# snow_depth_gauge_2D.net
KiCad netlist of a schematic drawn in EAGLE
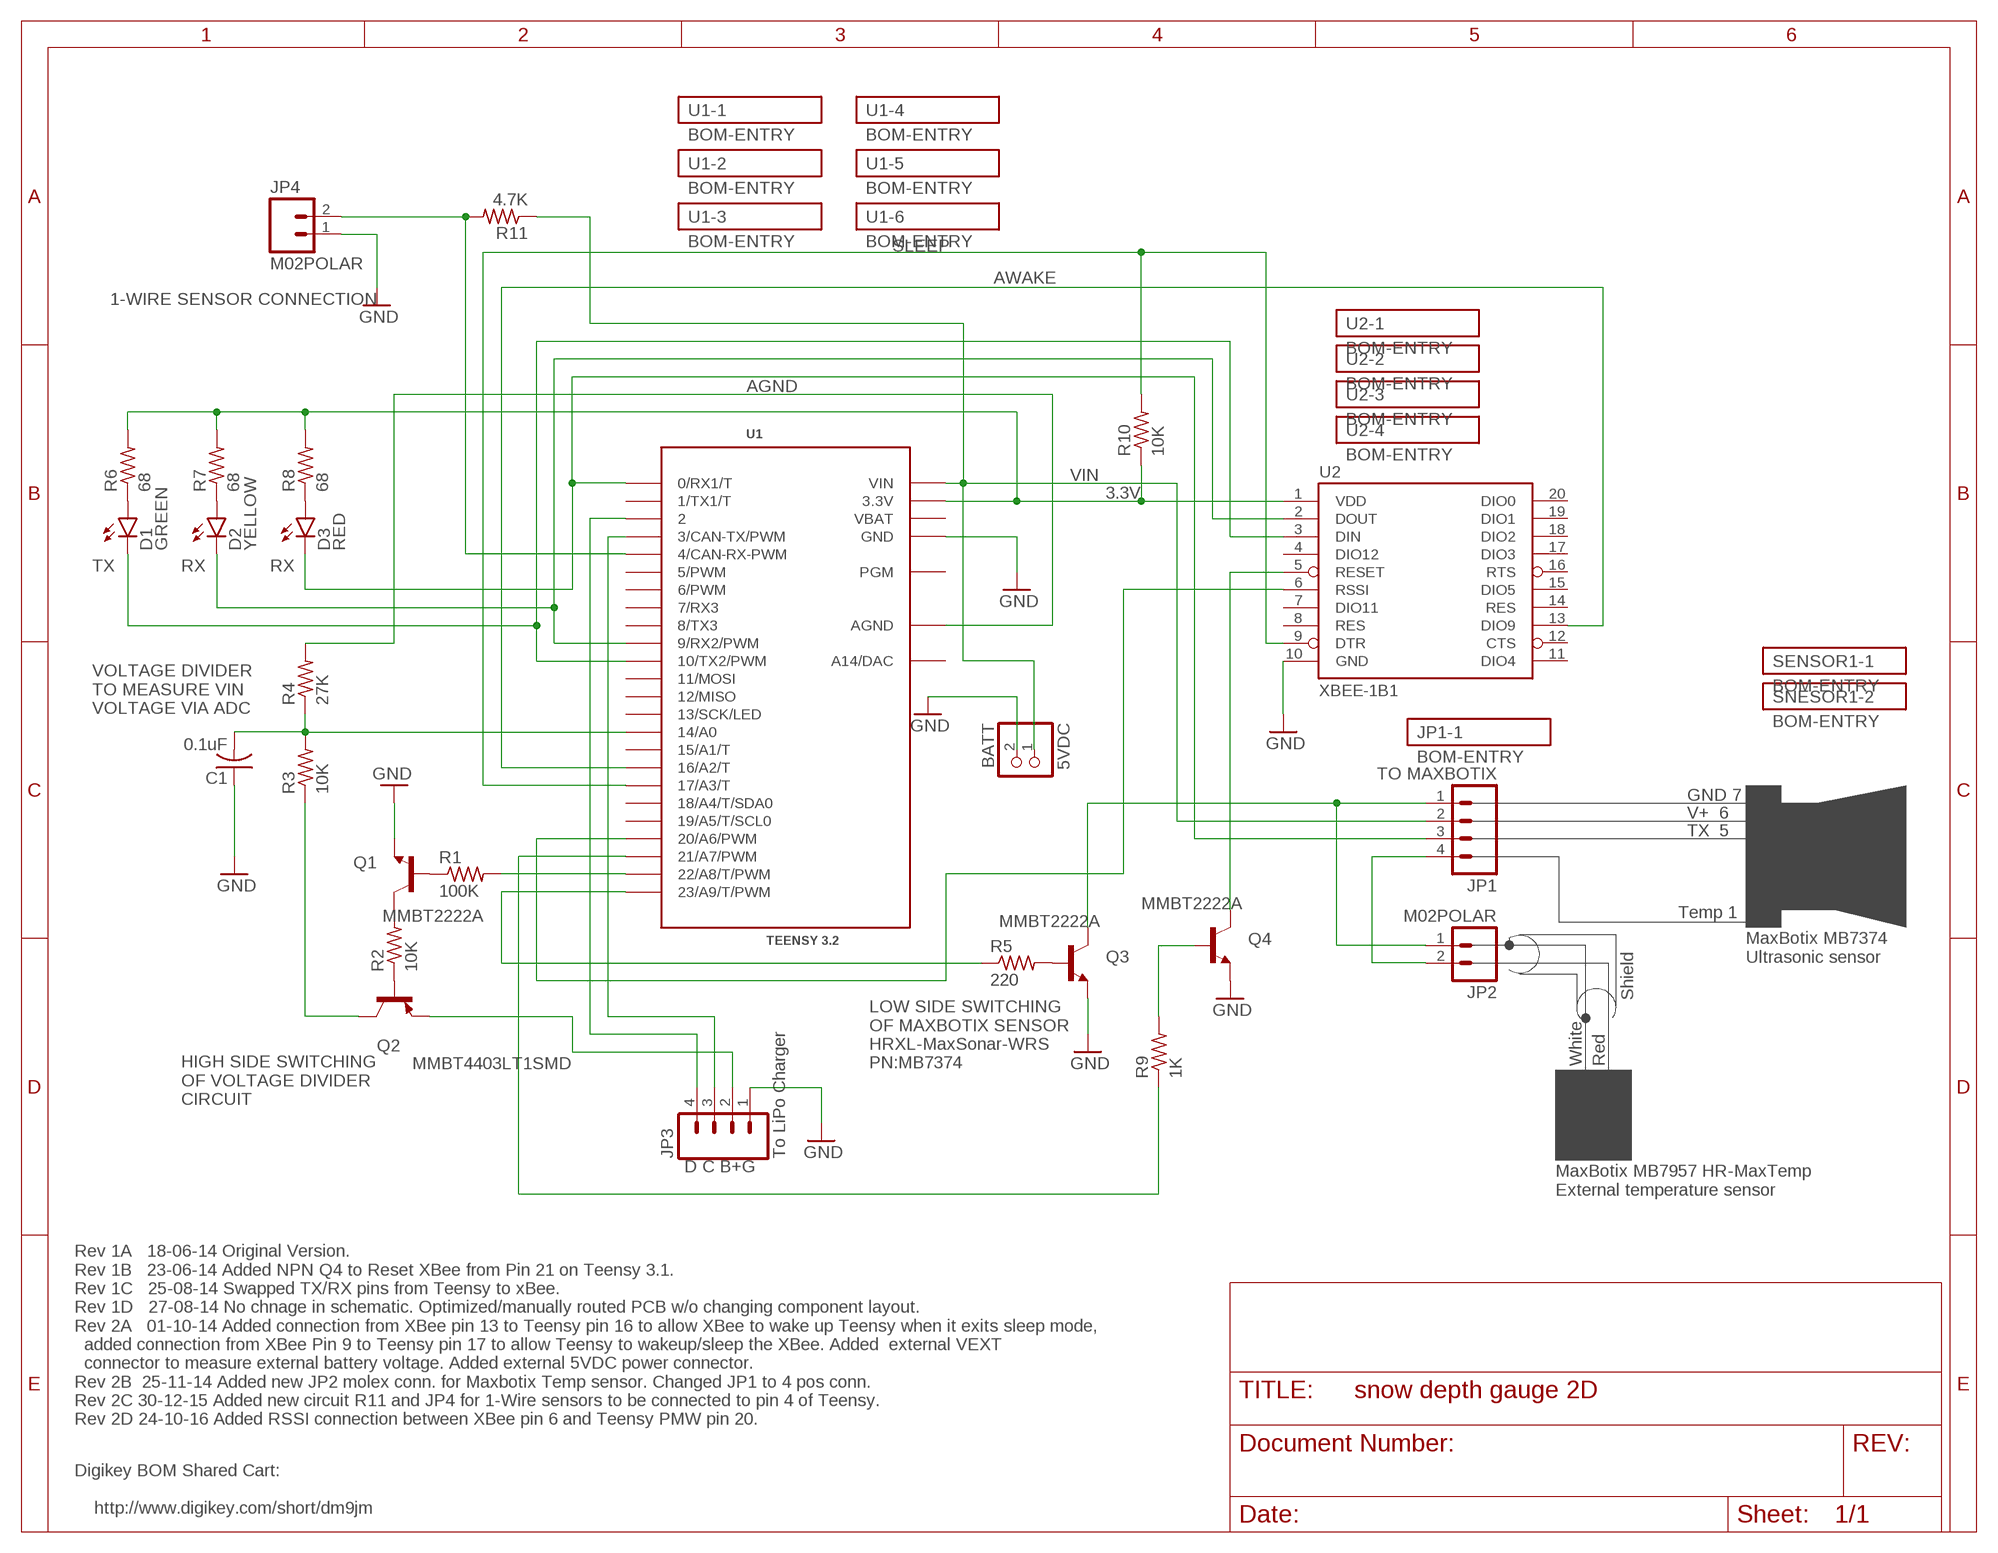
[diagram p0: schematic, sheet 1]

(export (version "E")
  (design (tool "Eeschema 10.0.6"))
  (components
    (comp (ref "BATT")
      (value "5VDC")
      (footprint "eagle-import:JST-PH-2-SMT-RA")
      (fields (field (name "PARTNO") "S2B-PH-SM4-TB(LF)(SN)"))
      (libsource (lib "eagle-import") (part "JST_2PIN-SMT-RA"))
    )
    (comp (ref "C1")
      (value "0.1uF")
      (footprint "eagle-import:C3216")
      (fields (field (name "PARTNO") "C1206C104K4RACTU"))
      (libsource (lib "eagle-import") (part "C-USC3216"))
    )
    (comp (ref "D1")
      (value "GREEN")
      (footprint "eagle-import:LED-0603")
      (fields (field (name "PARTNO") "LNJ337W83RA"))
      (libsource (lib "eagle-import") (part "LED-GREEN0603"))
    )
    (comp (ref "D2")
      (value "YELLOW")
      (footprint "eagle-import:LED-0603")
      (fields (field (name "PARTNO") "LNJ437W84RA"))
      (libsource (lib "eagle-import") (part "LED-YELLOW0603"))
    )
    (comp (ref "D3")
      (value "RED")
      (footprint "eagle-import:LED-0603")
      (fields (field (name "PARTNO") "LNJ237W82RA"))
      (libsource (lib "eagle-import") (part "LED-RED0603"))
    )
    (comp (ref "JP1")
      (value "TO MAXBOTIX")
      (footprint "eagle-import:MOLEX-1X4")
      (fields (field (name "PARTNO") "0022292041"))
      (libsource (lib "eagle-import") (part "M04POLAR"))
    )
    (comp (ref "JP2")
      (value "M02POLAR")
      (footprint "eagle-import:MOLEX-1X2")
      (fields (field (name "PARTNO") "0022292021"))
      (libsource (lib "eagle-import") (part "M02POLAR"))
    )
    (comp (ref "JP3")
      (value "To LiPo Charger")
      (footprint "eagle-import:MOLEX-1X4")
      (fields (field (name "PARTNO") "0022292041"))
      (libsource (lib "eagle-import") (part "M04POLAR"))
    )
    (comp (ref "JP4")
      (value "M02POLAR")
      (footprint "eagle-import:MOLEX-1X2")
      (fields (field (name "PARTNO") "0022292021"))
      (libsource (lib "eagle-import") (part "M02POLAR"))
    )
    (comp (ref "Q1")
      (value "MMBT2222A")
      (footprint "eagle-import:SOT23-BEC")
      (libsource (lib "eagle-import") (part "-NPN-SOT23-BECMMBT2222ALT1"))
    )
    (comp (ref "Q2")
      (value "MMBT4403LT1SMD")
      (footprint "eagle-import:SOT23-BEC")
      (fields (field (name "PARTNO") "MMBT4403"))
      (libsource (lib "eagle-import") (part "MMBT4403SMDLT1"))
    )
    (comp (ref "Q3")
      (value "MMBT2222A")
      (footprint "eagle-import:SOT23-BEC")
      (libsource (lib "eagle-import") (part "-NPN-SOT23-BECMMBT2222ALT1"))
    )
    (comp (ref "Q4")
      (value "MMBT2222A")
      (footprint "eagle-import:SOT23-BEC")
      (libsource (lib "eagle-import") (part "-NPN-SOT23-BECMMBT2222ALT1"))
    )
    (comp (ref "R1")
      (value "100K")
      (footprint "eagle-import:R3216")
      (fields (field (name "PARTNO") "KTR18EZPJ104"))
      (libsource (lib "eagle-import") (part "R-US_R3216"))
    )
    (comp (ref "R2")
      (value "10K")
      (footprint "eagle-import:R3216")
      (fields (field (name "PARTNO") "KTR18EZPJ103"))
      (libsource (lib "eagle-import") (part "R-US_R3216"))
    )
    (comp (ref "R3")
      (value "10K")
      (footprint "eagle-import:R3216")
      (fields (field (name "PARTNO") "KTR18EZPJ103"))
      (libsource (lib "eagle-import") (part "R-US_R3216"))
    )
    (comp (ref "R4")
      (value "27K")
      (footprint "eagle-import:R3216")
      (fields (field (name "PARTNO") "KTR18EZPJ273"))
      (libsource (lib "eagle-import") (part "R-US_R3216"))
    )
    (comp (ref "R5")
      (value "220")
      (footprint "eagle-import:R3216")
      (fields (field (name "PARTNO") "KTR18EZPJ221"))
      (libsource (lib "eagle-import") (part "R-US_R3216"))
    )
    (comp (ref "R6")
      (value "68")
      (footprint "eagle-import:R3216")
      (fields (field (name "PARTNO") "KTR18EZPF68R0"))
      (libsource (lib "eagle-import") (part "R-US_R3216"))
    )
    (comp (ref "R7")
      (value "68")
      (footprint "eagle-import:R3216")
      (fields (field (name "PARTNO") "KTR18EZPF68R0"))
      (libsource (lib "eagle-import") (part "R-US_R3216"))
    )
    (comp (ref "R8")
      (value "68")
      (footprint "eagle-import:R3216")
      (fields (field (name "PARTNO") "KTR18EZPF68R0"))
      (libsource (lib "eagle-import") (part "R-US_R3216"))
    )
    (comp (ref "R9")
      (value "1K")
      (footprint "eagle-import:R3216")
      (fields (field (name "PARTNO") "KTR18EZPJ102"))
      (libsource (lib "eagle-import") (part "R-US_R3216"))
    )
    (comp (ref "R10")
      (value "10K")
      (footprint "eagle-import:R3216")
      (fields (field (name "PARTNO") "KTR18EZPJ103"))
      (libsource (lib "eagle-import") (part "R-US_R3216"))
    )
    (comp (ref "R11")
      (value "4.7K")
      (footprint "eagle-import:R3216")
      (fields (field (name "PARTNO") "KTR18EZPF4701"))
      (libsource (lib "eagle-import") (part "R-US_R3216"))
    )
    (comp (ref "U1")
      (value "TEENSY 3.2")
      (footprint "eagle-import:TEENSY_3.1_BASIC")
      (fields (field (name "PARTNO") "TEENSY32"))
      (libsource (lib "eagle-import") (part "TEENSY_3.1_BASIC"))
    )
    (comp (ref "U2")
      (value "XBEE-1B1")
      (footprint "eagle-import:XBEE-1")
      (fields (field (name "PARTNO") "XB24-AUI-001"))
      (libsource (lib "eagle-import") (part "XBEE-1B1"))
    )
  )
  (nets
    (net (code "1") (name "/3.3V") (class "Default")
      (node (ref "R10") (pin "1") (pinfunction "1_1") (pintype "passive"))
      (node (ref "R6") (pin "2") (pinfunction "2_2") (pintype "passive"))
      (node (ref "R7") (pin "2") (pinfunction "2_2") (pintype "passive"))
      (node (ref "R8") (pin "2") (pinfunction "2_2") (pintype "passive"))
      (node (ref "U1") (pin "3.3V") (pinfunction "3.3V_3.3V") (pintype "power_in"))
      (node (ref "U1") (pin "3.3V1") (pinfunction "3.3V_3.3V1") (pintype "power_in"))
      (node (ref "U2") (pin "1") (pinfunction "VDD_1") (pintype "power_in"))
    )
    (net (code "2") (name "/AGND") (class "Default")
      (node (ref "R4") (pin "2") (pinfunction "2_2") (pintype "passive"))
      (node (ref "U1") (pin "AGND") (pinfunction "AGND_AGND") (pintype "power_in"))
    )
    (net (code "3") (name "/AWAKE") (class "Default")
      (node (ref "U1") (pin "16/A2") (pinfunction "16/A2/T_16/A2") (pintype "bidirectional"))
      (node (ref "U2") (pin "13") (pinfunction "DIO9_13") (pintype "bidirectional"))
    )
    (net (code "4") (name "/SLEEP") (class "Default")
      (node (ref "R10") (pin "2") (pinfunction "2_2") (pintype "passive"))
      (node (ref "U1") (pin "17/A3") (pinfunction "17/A3/T_17/A3") (pintype "bidirectional"))
      (node (ref "U2") (pin "9") (pinfunction "DTR_9") (pintype "bidirectional"))
    )
    (net (code "5") (name "/VBAT") (class "Default")
      (node (ref "U1") (pin "VBAT") (pinfunction "VBAT_VBAT") (pintype "power_in"))
    )
    (net (code "6") (name "/VIN") (class "Default")
      (node (ref "BATT") (pin "1") (pinfunction "2_1") (pintype "passive"))
      (node (ref "JP1") (pin "2") (pinfunction "2_2") (pintype "passive"))
      (node (ref "R11") (pin "1") (pinfunction "1_1") (pintype "passive"))
      (node (ref "U1") (pin "VIN") (pinfunction "VIN_VIN") (pintype "power_in"))
    )
    (net (code "7") (name "GND") (class "Default")
      (node (ref "BATT") (pin "2") (pinfunction "1_2") (pintype "passive"))
      (node (ref "C1") (pin "1") (pinfunction "1_1") (pintype "passive"))
      (node (ref "JP3") (pin "1") (pinfunction "1_1") (pintype "passive"))
      (node (ref "JP4") (pin "1") (pinfunction "1_1") (pintype "passive"))
      (node (ref "Q1") (pin "E") (pinfunction "E_E") (pintype "passive"))
      (node (ref "Q3") (pin "E") (pinfunction "E_E") (pintype "passive"))
      (node (ref "Q4") (pin "E") (pinfunction "E_E") (pintype "passive"))
      (node (ref "U1") (pin "GND") (pinfunction "GND_GND") (pintype "power_in"))
      (node (ref "U1") (pin "GND1") (pinfunction "GND_GND1") (pintype "power_in"))
      (node (ref "U2") (pin "10") (pinfunction "GND_10") (pintype "power_in"))
    )
    (net (code "8") (name "Net-(C1-Pad2)") (class "Default")
      (node (ref "C1") (pin "2") (pinfunction "2_2") (pintype "passive"))
      (node (ref "R3") (pin "2") (pinfunction "2_2") (pintype "passive"))
      (node (ref "R4") (pin "1") (pinfunction "1_1") (pintype "passive"))
      (node (ref "U1") (pin "14/A0") (pinfunction "14/A0_14/A0") (pintype "bidirectional"))
    )
    (net (code "9") (name "Net-(D1-PadA)") (class "Default")
      (node (ref "D1") (pin "A") (pinfunction "A_A") (pintype "passive"))
      (node (ref "R6") (pin "1") (pinfunction "1_1") (pintype "passive"))
    )
    (net (code "10") (name "Net-(D2-PadA)") (class "Default")
      (node (ref "D2") (pin "A") (pinfunction "A_A") (pintype "passive"))
      (node (ref "R7") (pin "1") (pinfunction "1_1") (pintype "passive"))
    )
    (net (code "11") (name "Net-(D3-PadA)") (class "Default")
      (node (ref "D3") (pin "A") (pinfunction "A_A") (pintype "passive"))
      (node (ref "R8") (pin "1") (pinfunction "1_1") (pintype "passive"))
    )
    (net (code "12") (name "Net-(JP1-Pad1)") (class "Default")
      (node (ref "JP1") (pin "1") (pinfunction "1_1") (pintype "passive"))
      (node (ref "JP2") (pin "1") (pinfunction "1_1") (pintype "passive"))
      (node (ref "Q3") (pin "C") (pinfunction "C_C") (pintype "passive"))
    )
    (net (code "13") (name "Net-(JP1-Pad4)") (class "Default")
      (node (ref "JP1") (pin "4") (pinfunction "4_4") (pintype "passive"))
      (node (ref "JP2") (pin "2") (pinfunction "2_2") (pintype "passive"))
    )
    (net (code "14") (name "Net-(JP3-Pad2)") (class "Default")
      (node (ref "JP3") (pin "2") (pinfunction "2_2") (pintype "passive"))
      (node (ref "Q2") (pin "E") (pinfunction "E_E") (pintype "passive"))
    )
    (net (code "15") (name "Net-(JP3-Pad4)") (class "Default")
      (node (ref "JP3") (pin "4") (pinfunction "4_4") (pintype "passive"))
      (node (ref "U1") (pin "2") (pinfunction "2_2") (pintype "bidirectional"))
    )
    (net (code "16") (name "Net-(Q1-PadB)") (class "Default")
      (node (ref "Q1") (pin "B") (pinfunction "B_B") (pintype "passive"))
      (node (ref "R1") (pin "1") (pinfunction "1_1") (pintype "passive"))
    )
    (net (code "17") (name "Net-(Q1-PadC)") (class "Default")
      (node (ref "Q1") (pin "C") (pinfunction "C_C") (pintype "passive"))
      (node (ref "R2") (pin "2") (pinfunction "2_2") (pintype "passive"))
    )
    (net (code "18") (name "Net-(Q2-PadB)") (class "Default")
      (node (ref "Q2") (pin "B") (pinfunction "B_B") (pintype "passive"))
      (node (ref "R2") (pin "1") (pinfunction "1_1") (pintype "passive"))
    )
    (net (code "19") (name "Net-(Q2-PadC)") (class "Default")
      (node (ref "Q2") (pin "C") (pinfunction "C_C") (pintype "passive"))
      (node (ref "R3") (pin "1") (pinfunction "1_1") (pintype "passive"))
    )
    (net (code "20") (name "Net-(Q3-PadB)") (class "Default")
      (node (ref "Q3") (pin "B") (pinfunction "B_B") (pintype "passive"))
      (node (ref "R5") (pin "2") (pinfunction "2_2") (pintype "passive"))
    )
    (net (code "21") (name "Net-(Q4-PadB)") (class "Default")
      (node (ref "Q4") (pin "B") (pinfunction "B_B") (pintype "passive"))
      (node (ref "R9") (pin "2") (pinfunction "2_2") (pintype "passive"))
    )
    (net (code "22") (name "Net-(U1-0{slash}RX1{slash}T)") (class "Default")
      (node (ref "D3") (pin "C") (pinfunction "C_C") (pintype "passive"))
      (node (ref "JP1") (pin "3") (pinfunction "3_3") (pintype "passive"))
      (node (ref "U1") (pin "0") (pinfunction "0/RX1/T_0") (pintype "bidirectional"))
    )
    (net (code "23") (name "Net-(U1-3{slash}CAN-TX{slash}PWM)") (class "Default")
      (node (ref "JP3") (pin "3") (pinfunction "3_3") (pintype "passive"))
      (node (ref "U1") (pin "3") (pinfunction "3/CAN-TX/PWM_3") (pintype "bidirectional"))
    )
    (net (code "24") (name "Net-(U1-4{slash}CAN-RX-PWM)") (class "Default")
      (node (ref "JP4") (pin "2") (pinfunction "2_2") (pintype "passive"))
      (node (ref "R11") (pin "2") (pinfunction "2_2") (pintype "passive"))
      (node (ref "U1") (pin "4") (pinfunction "4/CAN-RX-PWM_4") (pintype "bidirectional"))
    )
    (net (code "25") (name "Net-(U1-9{slash}RX2{slash}PWM)") (class "Default")
      (node (ref "D2") (pin "C") (pinfunction "C_C") (pintype "passive"))
      (node (ref "U1") (pin "9") (pinfunction "9/RX2/PWM_9") (pintype "bidirectional"))
      (node (ref "U2") (pin "2") (pinfunction "DOUT_2") (pintype "output"))
    )
    (net (code "26") (name "Net-(U1-10{slash}TX2{slash}PWM)") (class "Default")
      (node (ref "D1") (pin "C") (pinfunction "C_C") (pintype "passive"))
      (node (ref "U1") (pin "10") (pinfunction "10/TX2/PWM_10") (pintype "bidirectional"))
      (node (ref "U2") (pin "3") (pinfunction "DIN_3") (pintype "input"))
    )
    (net (code "27") (name "Net-(U1-20{slash}A6{slash}PWM)") (class "Default")
      (node (ref "U1") (pin "20/A6") (pinfunction "20/A6/PWM_20/A6") (pintype "bidirectional"))
      (node (ref "U2") (pin "6") (pinfunction "RSSI_6") (pintype "bidirectional"))
    )
    (net (code "28") (name "Net-(U1-21{slash}A7{slash}PWM)") (class "Default")
      (node (ref "R9") (pin "1") (pinfunction "1_1") (pintype "passive"))
      (node (ref "U1") (pin "21/A7") (pinfunction "21/A7/PWM_21/A7") (pintype "bidirectional"))
    )
    (net (code "29") (name "Net-(U1-22{slash}A8{slash}T{slash}PWM)") (class "Default")
      (node (ref "R1") (pin "2") (pinfunction "2_2") (pintype "passive"))
      (node (ref "U1") (pin "22/A8") (pinfunction "22/A8/T/PWM_22/A8") (pintype "bidirectional"))
    )
    (net (code "30") (name "Net-(U1-23{slash}A9{slash}T{slash}PWM)") (class "Default")
      (node (ref "R5") (pin "1") (pinfunction "1_1") (pintype "passive"))
      (node (ref "U1") (pin "23/A9") (pinfunction "23/A9/T/PWM_23/A9") (pintype "bidirectional"))
    )
    (net (code "31") (name "Net-(U2-RESET)") (class "Default")
      (node (ref "Q4") (pin "C") (pinfunction "C_C") (pintype "passive"))
      (node (ref "U2") (pin "5") (pinfunction "RESET_5") (pintype "input"))
    )
    (net (code "32") (name "unconnected-(U1-1{slash}TX1{slash}T-Pad1)") (class "Default")
      (node (ref "U1") (pin "1") (pinfunction "1/TX1/T_1") (pintype "bidirectional"))
    )
    (net (code "33") (name "unconnected-(U1-5{slash}PWM-Pad5)") (class "Default")
      (node (ref "U1") (pin "5") (pinfunction "5/PWM_5") (pintype "bidirectional"))
    )
    (net (code "34") (name "unconnected-(U1-6{slash}PWM-Pad6)") (class "Default")
      (node (ref "U1") (pin "6") (pinfunction "6/PWM_6") (pintype "bidirectional"))
    )
    (net (code "35") (name "unconnected-(U1-7{slash}RX3-Pad7)") (class "Default")
      (node (ref "U1") (pin "7") (pinfunction "7/RX3_7") (pintype "bidirectional"))
    )
    (net (code "36") (name "unconnected-(U1-8{slash}TX3-Pad8)") (class "Default")
      (node (ref "U1") (pin "8") (pinfunction "8/TX3_8") (pintype "bidirectional"))
    )
    (net (code "37") (name "unconnected-(U1-11{slash}MOSI-Pad11)") (class "Default")
      (node (ref "U1") (pin "11") (pinfunction "11/MOSI_11") (pintype "bidirectional"))
    )
    (net (code "38") (name "unconnected-(U1-12{slash}MISO-Pad12)") (class "Default")
      (node (ref "U1") (pin "12") (pinfunction "12/MISO_12") (pintype "bidirectional"))
    )
    (net (code "39") (name "unconnected-(U1-13{slash}SCK{slash}LED-Pad13)") (class "Default")
      (node (ref "U1") (pin "13") (pinfunction "13/SCK/LED_13") (pintype "bidirectional"))
    )
    (net (code "40") (name "unconnected-(U1-15{slash}A1{slash}T-Pad15{slash}A1)") (class "Default")
      (node (ref "U1") (pin "15/A1") (pinfunction "15/A1/T_15/A1") (pintype "bidirectional"))
    )
    (net (code "41") (name "unconnected-(U1-18{slash}A4{slash}T{slash}SDA0-Pad18{slash}A4)") (class "Default")
      (node (ref "U1") (pin "18/A4") (pinfunction "18/A4/T/SDA0_18/A4") (pintype "bidirectional"))
    )
    (net (code "42") (name "unconnected-(U1-19{slash}A5{slash}T{slash}SCL0-Pad19{slash}A5)") (class "Default")
      (node (ref "U1") (pin "19/A5") (pinfunction "19/A5/T/SCL0_19/A5") (pintype "bidirectional"))
    )
    (net (code "43") (name "unconnected-(U1-A14{slash}DAC-PadA14)") (class "Default")
      (node (ref "U1") (pin "A14") (pinfunction "A14/DAC_A14") (pintype "bidirectional"))
    )
    (net (code "44") (name "unconnected-(U1-PadPGM)") (class "Default")
      (node (ref "U1") (pin "PGM") (pinfunction "PGM_PGM") (pintype "bidirectional"))
    )
    (net (code "45") (name "unconnected-(U2-CTS-Pad12)") (class "Default")
      (node (ref "U2") (pin "12") (pinfunction "CTS_12") (pintype "output"))
    )
    (net (code "46") (name "unconnected-(U2-DIO0-Pad20)") (class "Default")
      (node (ref "U2") (pin "20") (pinfunction "DIO0_20") (pintype "bidirectional"))
    )
    (net (code "47") (name "unconnected-(U2-DIO1-Pad19)") (class "Default")
      (node (ref "U2") (pin "19") (pinfunction "DIO1_19") (pintype "bidirectional"))
    )
    (net (code "48") (name "unconnected-(U2-DIO2-Pad18)") (class "Default")
      (node (ref "U2") (pin "18") (pinfunction "DIO2_18") (pintype "bidirectional"))
    )
    (net (code "49") (name "unconnected-(U2-DIO3-Pad17)") (class "Default")
      (node (ref "U2") (pin "17") (pinfunction "DIO3_17") (pintype "bidirectional"))
    )
    (net (code "50") (name "unconnected-(U2-DIO4-Pad11)") (class "Default")
      (node (ref "U2") (pin "11") (pinfunction "DIO4_11") (pintype "bidirectional"))
    )
    (net (code "51") (name "unconnected-(U2-DIO5-Pad15)") (class "Default")
      (node (ref "U2") (pin "15") (pinfunction "DIO5_15") (pintype "bidirectional"))
    )
    (net (code "52") (name "unconnected-(U2-DIO11-Pad7)") (class "Default")
      (node (ref "U2") (pin "7") (pinfunction "DIO11_7") (pintype "bidirectional"))
    )
    (net (code "53") (name "unconnected-(U2-DIO12-Pad4)") (class "Default")
      (node (ref "U2") (pin "4") (pinfunction "DIO12_4") (pintype "bidirectional"))
    )
    (net (code "54") (name "unconnected-(U2-RES-Pad8)") (class "Default")
      (node (ref "U2") (pin "8") (pinfunction "RES_8") (pintype "bidirectional"))
    )
    (net (code "55") (name "unconnected-(U2-RES-Pad14)") (class "Default")
      (node (ref "U2") (pin "14") (pinfunction "RES_14") (pintype "bidirectional"))
    )
    (net (code "56") (name "unconnected-(U2-RTS-Pad16)") (class "Default")
      (node (ref "U2") (pin "16") (pinfunction "RTS_16") (pintype "input"))
    )
  )
)
